# full_motor.net
KiCad netlist of a schematic drawn in EAGLE
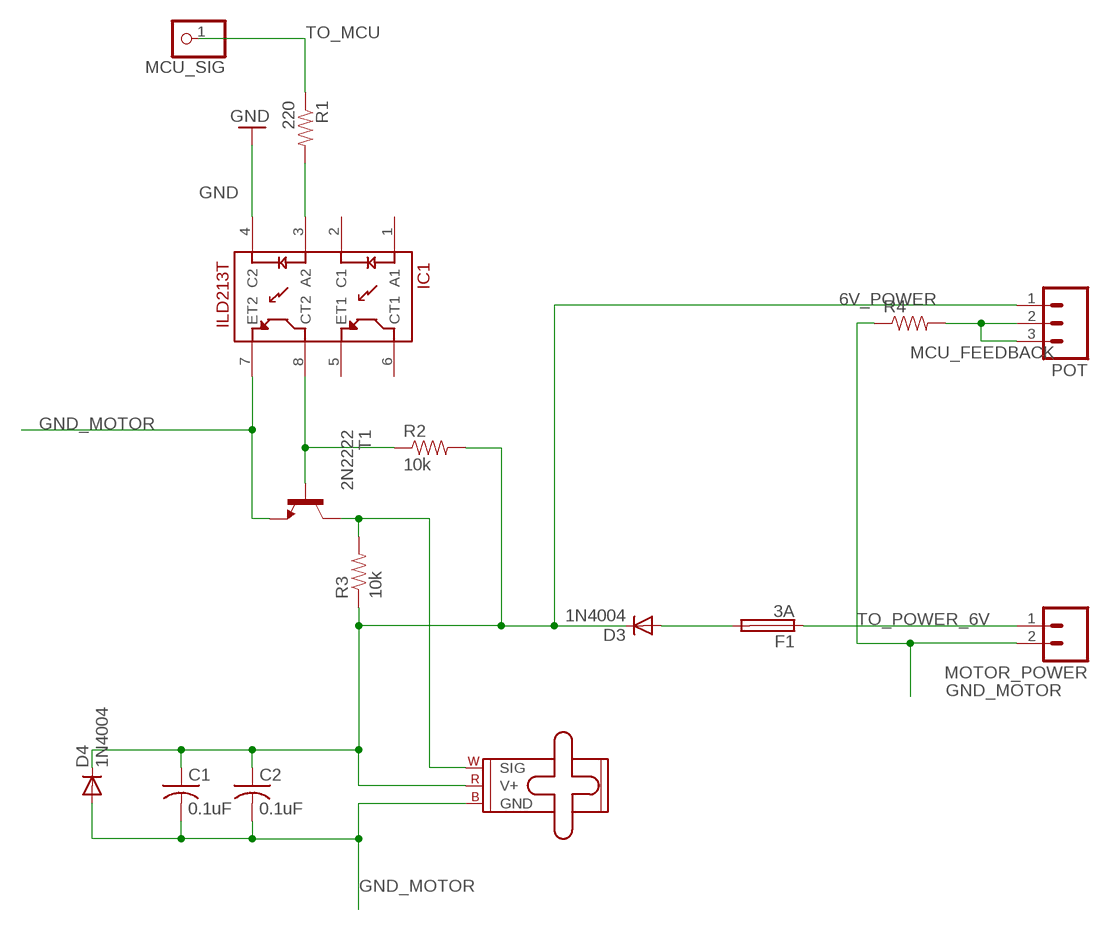
[diagram p0: schematic, sheet 1]

(export (version "E")
  (design (tool "Eeschema 10.0.6"))
  (components
    (comp (ref "C1")
      (value "0.1uF")
      (footprint "eagle-import:C025-024X044")
      (libsource (lib "eagle-import") (part "C-US025-024X044"))
    )
    (comp (ref "C2")
      (value "0.1uF")
      (footprint "eagle-import:C025-024X044")
      (libsource (lib "eagle-import") (part "C-US025-024X044"))
    )
    (comp (ref "D3")
      (value "1N4004")
      (footprint "eagle-import:DO41-10")
      (libsource (lib "eagle-import") (part "1N4004"))
    )
    (comp (ref "D4")
      (value "1N4004")
      (footprint "eagle-import:DO41-10")
      (libsource (lib "eagle-import") (part "1N4004"))
    )
    (comp (ref "F1")
      (value "3A")
      (footprint "eagle-import:TE5")
      (libsource (lib "eagle-import") (part "TE5"))
    )
    (comp (ref "IC1")
      (value "ILD213T")
      (footprint "eagle-import:SO08")
      (libsource (lib "eagle-import") (part "ILD213T"))
    )
    (comp (ref "MCU_SIG")
      (value "PINHD-1X1")
      (footprint "eagle-import:1X01")
      (libsource (lib "eagle-import") (part "PINHD-1X1"))
    )
    (comp (ref "MOTOR_POWER")
      (value "M02PTH")
      (footprint "eagle-import:1X02")
      (libsource (lib "eagle-import") (part "M02PTH"))
    )
    (comp (ref "POT")
      (value "M03PTH")
      (footprint "eagle-import:1X03")
      (libsource (lib "eagle-import") (part "M03PTH"))
    )
    (comp (ref "R1")
      (value "220")
      (footprint "eagle-import:AXIAL-0.3EZ")
      (libsource (lib "eagle-import") (part "RESISTOREZ"))
    )
    (comp (ref "R2")
      (value "10k")
      (footprint "eagle-import:AXIAL-0.3EZ")
      (libsource (lib "eagle-import") (part "RESISTOREZ"))
    )
    (comp (ref "R3")
      (value "10k")
      (footprint "eagle-import:AXIAL-0.3EZ")
      (libsource (lib "eagle-import") (part "RESISTOREZ"))
    )
    (comp (ref "R4")
      (value "RESISTOREZ")
      (footprint "eagle-import:AXIAL-0.3EZ")
      (libsource (lib "eagle-import") (part "RESISTOREZ"))
    )
    (comp (ref "SERVO")
      (value "SMALL_SERVO")
      (footprint "eagle-import:1X03")
      (libsource (lib "eagle-import") (part "SMALL_SERVO"))
    )
    (comp (ref "T1")
      (value "2N2222")
      (footprint "eagle-import:TO92-EBC-OVAL")
      (libsource (lib "eagle-import") (part "2N2222"))
    )
  )
  (nets
    (net (code "1") (name "/6V_POWER") (class "Default")
      (node (ref "C1") (pin "1") (pinfunction "1_1") (pintype "passive"))
      (node (ref "C2") (pin "1") (pinfunction "1_1") (pintype "passive"))
      (node (ref "D3") (pin "C") (pinfunction "C_C") (pintype "passive"))
      (node (ref "D4") (pin "C") (pinfunction "C_C") (pintype "passive"))
      (node (ref "POT") (pin "1") (pinfunction "1_1") (pintype "passive"))
      (node (ref "R2") (pin "P$2") (pinfunction "2_P$2") (pintype "passive"))
      (node (ref "R3") (pin "P$1") (pinfunction "1_P$1") (pintype "passive"))
      (node (ref "SERVO") (pin "2") (pinfunction "V+_2") (pintype "bidirectional"))
    )
    (net (code "2") (name "/GND_MOTOR") (class "Default")
      (node (ref "C1") (pin "2") (pinfunction "2_2") (pintype "passive"))
      (node (ref "C2") (pin "2") (pinfunction "2_2") (pintype "passive"))
      (node (ref "D4") (pin "A") (pinfunction "A_A") (pintype "passive"))
      (node (ref "IC1") (pin "7") (pinfunction "ET2_7") (pintype "bidirectional"))
      (node (ref "MOTOR_POWER") (pin "2") (pinfunction "2_2") (pintype "passive"))
      (node (ref "R4") (pin "P$1") (pinfunction "1_P$1") (pintype "passive"))
      (node (ref "SERVO") (pin "3") (pinfunction "GND_3") (pintype "bidirectional"))
      (node (ref "T1") (pin "E") (pinfunction "E_E") (pintype "passive"))
    )
    (net (code "3") (name "/MCU_FEEDBACK") (class "Default")
      (node (ref "POT") (pin "2") (pinfunction "2_2") (pintype "passive"))
      (node (ref "POT") (pin "3") (pinfunction "3_3") (pintype "passive"))
      (node (ref "R4") (pin "P$2") (pinfunction "2_P$2") (pintype "passive"))
    )
    (net (code "4") (name "/TO_MCU") (class "Default")
      (node (ref "MCU_SIG") (pin "1") (pinfunction "1_1") (pintype "passive"))
      (node (ref "R1") (pin "P$1") (pinfunction "1_P$1") (pintype "passive"))
    )
    (net (code "5") (name "/TO_POWER_6V") (class "Default")
      (node (ref "F1") (pin "1") (pinfunction "1_1") (pintype "passive"))
      (node (ref "MOTOR_POWER") (pin "1") (pinfunction "1_1") (pintype "passive"))
    )
    (net (code "6") (name "GND") (class "Default")
      (node (ref "IC1") (pin "4") (pinfunction "C2_4") (pintype "bidirectional"))
    )
    (net (code "7") (name "Net-(D3-PadA)") (class "Default")
      (node (ref "D3") (pin "A") (pinfunction "A_A") (pintype "passive"))
      (node (ref "F1") (pin "2") (pinfunction "2_2") (pintype "passive"))
    )
    (net (code "8") (name "Net-(IC1-A2)") (class "Default")
      (node (ref "IC1") (pin "3") (pinfunction "A2_3") (pintype "bidirectional"))
      (node (ref "R1") (pin "P$2") (pinfunction "2_P$2") (pintype "passive"))
    )
    (net (code "9") (name "Net-(IC1-CT2)") (class "Default")
      (node (ref "IC1") (pin "8") (pinfunction "CT2_8") (pintype "bidirectional"))
      (node (ref "R2") (pin "P$1") (pinfunction "1_P$1") (pintype "passive"))
      (node (ref "T1") (pin "B") (pinfunction "B_B") (pintype "passive"))
    )
    (net (code "10") (name "Net-(R3-2)") (class "Default")
      (node (ref "R3") (pin "P$2") (pinfunction "2_P$2") (pintype "passive"))
      (node (ref "SERVO") (pin "1") (pinfunction "SIG_1") (pintype "bidirectional"))
      (node (ref "T1") (pin "C") (pinfunction "C_C") (pintype "passive"))
    )
    (net (code "11") (name "unconnected-(IC1-A1-Pad1)") (class "Default")
      (node (ref "IC1") (pin "1") (pinfunction "A1_1") (pintype "bidirectional"))
    )
    (net (code "12") (name "unconnected-(IC1-C1-Pad2)") (class "Default")
      (node (ref "IC1") (pin "2") (pinfunction "C1_2") (pintype "bidirectional"))
    )
    (net (code "13") (name "unconnected-(IC1-CT1-Pad6)") (class "Default")
      (node (ref "IC1") (pin "6") (pinfunction "CT1_6") (pintype "bidirectional"))
    )
    (net (code "14") (name "unconnected-(IC1-ET1-Pad5)") (class "Default")
      (node (ref "IC1") (pin "5") (pinfunction "ET1_5") (pintype "bidirectional"))
    )
  )
)
